# LB_BIT_i16_PULSE-v02_rev1.net
KiCad netlist of a schematic drawn in EAGLE
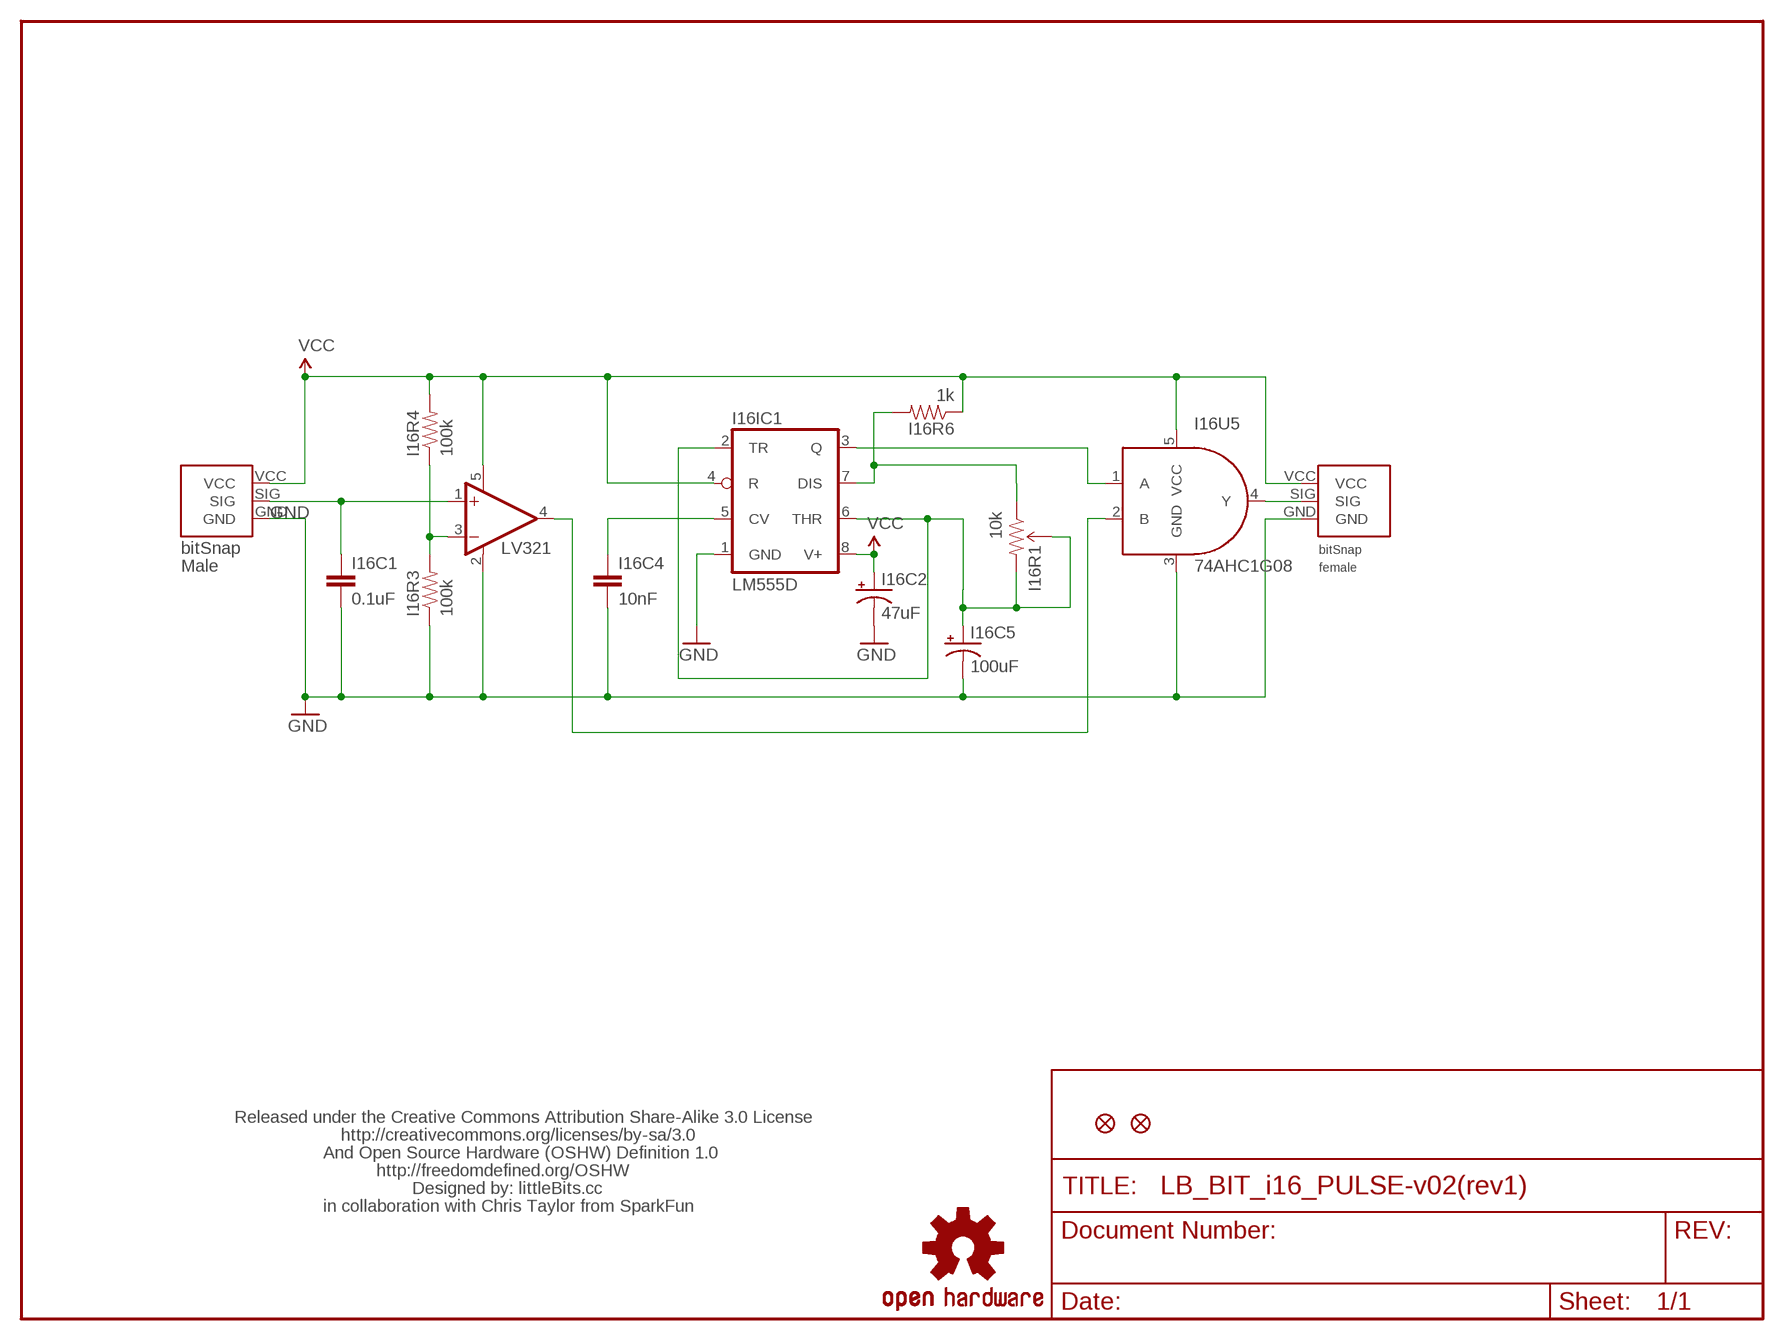
[diagram p0: schematic, sheet 1]

(export (version "E")
  (design (tool "Eeschema 10.0.6"))
  (components
    (comp (ref "I16BSF")
      (value "BITSNAP_FEMALE")
      (footprint "eagle-import:BITSNAP_FEMALE")
      (libsource (lib "eagle-import") (part "BITSNAP_FEMALE"))
    )
    (comp (ref "I16BSM")
      (value "BITSNAP_MALE")
      (footprint "eagle-import:BITSNAP_MALE")
      (libsource (lib "eagle-import") (part "BITSNAP_MALE"))
    )
    (comp (ref "I16C1")
      (value "0.1uF")
      (footprint "eagle-import:0603-CAP")
      (libsource (lib "eagle-import") (part "CAP0603-CAP"))
    )
    (comp (ref "I16C2")
      (value "47uF")
      (footprint "eagle-import:EIA3528")
      (libsource (lib "eagle-import") (part "CAP_POL3528"))
    )
    (comp (ref "I16C4")
      (value "10nF")
      (footprint "eagle-import:0603-CAP")
      (libsource (lib "eagle-import") (part "CAP0603-CAP"))
    )
    (comp (ref "I16C5")
      (value "100uF")
      (footprint "eagle-import:PANASONIC_C")
      (libsource (lib "eagle-import") (part "CAP_POLC"))
    )
    (comp (ref "I16IC1")
      (value "LM555D")
      (footprint "eagle-import:SO08")
      (libsource (lib "eagle-import") (part "555DLM"))
    )
    (comp (ref "I16R1")
      (value "10k")
      (footprint "eagle-import:TRIMPOT-3MM")
      (libsource (lib "eagle-import") (part "TRIMPOTSMD"))
    )
    (comp (ref "I16R3")
      (value "100k")
      (footprint "eagle-import:0603-RES")
      (libsource (lib "eagle-import") (part "RESISTOR0603-RES"))
    )
    (comp (ref "I16R4")
      (value "100k")
      (footprint "eagle-import:0603-RES")
      (libsource (lib "eagle-import") (part "RESISTOR0603-RES"))
    )
    (comp (ref "I16R6")
      (value "1k")
      (footprint "eagle-import:0603-RES")
      (libsource (lib "eagle-import") (part "RESISTOR0603-RES"))
    )
    (comp (ref "I16U1")
      (value "LV321")
      (footprint "eagle-import:SC70")
      (libsource (lib "eagle-import") (part "LV321"))
    )
    (comp (ref "I16U5")
      (value "74AHC1G08")
      (footprint "eagle-import:SOT23-5")
      (libsource (lib "eagle-import") (part "74AHC1G08"))
    )
    (comp (ref "JP1")
      (value "FIDUCIAL1X2.5")
      (footprint "eagle-import:FIDUCIAL-1X2.5")
      (libsource (lib "eagle-import") (part "FIDUCIAL1X2.5"))
    )
    (comp (ref "JP2")
      (value "FIDUCIAL1X2.5")
      (footprint "eagle-import:FIDUCIAL-1X2.5")
      (libsource (lib "eagle-import") (part "FIDUCIAL1X2.5"))
    )
    (comp (ref "U$1")
      (value "LB_CREDITS")
      (footprint "eagle-import:OSHWCREDIT")
      (libsource (lib "eagle-import") (part "LB_CREDITS"))
    )
    (comp (ref "U$5")
      (value "OSHW-LOGOL")
      (footprint "eagle-import:OSHW-LOGO-L")
      (libsource (lib "eagle-import") (part "OSHW-LOGOL"))
    )
  )
  (nets
    (net (code "1") (name "GND") (class "Default")
      (node (ref "I16BSF") (pin "GND") (pinfunction "GND_GND") (pintype "bidirectional"))
      (node (ref "I16BSM") (pin "GND") (pinfunction "GND_GND") (pintype "bidirectional"))
      (node (ref "I16C1") (pin "2") (pinfunction "2_2") (pintype "passive"))
      (node (ref "I16C2") (pin "C") (pinfunction "-_C") (pintype "passive"))
      (node (ref "I16C4") (pin "2") (pinfunction "2_2") (pintype "passive"))
      (node (ref "I16C5") (pin "-") (pinfunction "-_-") (pintype "passive"))
      (node (ref "I16IC1") (pin "1") (pinfunction "GND_1") (pintype "power_in"))
      (node (ref "I16R3") (pin "1") (pinfunction "1_1") (pintype "passive"))
      (node (ref "I16U1") (pin "2") (pinfunction "V-_2") (pintype "power_in"))
      (node (ref "I16U5") (pin "3") (pinfunction "GND_3") (pintype "bidirectional"))
    )
    (net (code "2") (name "Net-(I16IC1-CV)") (class "Default")
      (node (ref "I16C4") (pin "1") (pinfunction "1_1") (pintype "passive"))
      (node (ref "I16IC1") (pin "5") (pinfunction "CV_5") (pintype "input"))
    )
    (net (code "3") (name "Net-(I16IC1-DIS)") (class "Default")
      (node (ref "I16IC1") (pin "7") (pinfunction "DIS_7") (pintype "input"))
      (node (ref "I16R1") (pin "1") (pinfunction "CCW_1") (pintype "passive"))
      (node (ref "I16R6") (pin "2") (pinfunction "2_2") (pintype "passive"))
    )
    (net (code "4") (name "Net-(I16IC1-Q)") (class "Default")
      (node (ref "I16IC1") (pin "3") (pinfunction "Q_3") (pintype "output"))
      (node (ref "I16U5") (pin "1") (pinfunction "A_1") (pintype "bidirectional"))
    )
    (net (code "5") (name "Net-(I16IC1-THR)") (class "Default")
      (node (ref "I16C5") (pin "+") (pinfunction "+_+") (pintype "passive"))
      (node (ref "I16IC1") (pin "2") (pinfunction "TR_2") (pintype "input"))
      (node (ref "I16IC1") (pin "6") (pinfunction "THR_6") (pintype "input"))
      (node (ref "I16R1") (pin "2") (pinfunction "WIPER_2") (pintype "passive"))
      (node (ref "I16R1") (pin "3") (pinfunction "CW_3") (pintype "passive"))
    )
    (net (code "6") (name "Net-(I16U1-+IN)") (class "Default")
      (node (ref "I16BSM") (pin "SIG") (pinfunction "SIG_SIG") (pintype "bidirectional"))
      (node (ref "I16C1") (pin "1") (pinfunction "1_1") (pintype "passive"))
      (node (ref "I16U1") (pin "1") (pinfunction "+IN_1") (pintype "input"))
    )
    (net (code "7") (name "Net-(I16U1--IN)") (class "Default")
      (node (ref "I16R3") (pin "2") (pinfunction "2_2") (pintype "passive"))
      (node (ref "I16R4") (pin "1") (pinfunction "1_1") (pintype "passive"))
      (node (ref "I16U1") (pin "3") (pinfunction "-IN_3") (pintype "input"))
    )
    (net (code "8") (name "Net-(I16U1-OUT)") (class "Default")
      (node (ref "I16U1") (pin "4") (pinfunction "OUT_4") (pintype "output"))
      (node (ref "I16U5") (pin "2") (pinfunction "B_2") (pintype "bidirectional"))
    )
    (net (code "9") (name "Net-(I16U5-Y)") (class "Default")
      (node (ref "I16BSF") (pin "SIG") (pinfunction "SIG_SIG") (pintype "bidirectional"))
      (node (ref "I16U5") (pin "4") (pinfunction "Y_4") (pintype "bidirectional"))
    )
    (net (code "10") (name "VCC") (class "Default")
      (node (ref "I16BSF") (pin "VCC") (pinfunction "VCC_VCC") (pintype "bidirectional"))
      (node (ref "I16BSM") (pin "VCC") (pinfunction "VCC_VCC") (pintype "bidirectional"))
      (node (ref "I16C2") (pin "A") (pinfunction "+_A") (pintype "passive"))
      (node (ref "I16IC1") (pin "4") (pinfunction "R_4") (pintype "input"))
      (node (ref "I16IC1") (pin "8") (pinfunction "V+_8") (pintype "power_in"))
      (node (ref "I16R4") (pin "2") (pinfunction "2_2") (pintype "passive"))
      (node (ref "I16R6") (pin "1") (pinfunction "1_1") (pintype "passive"))
      (node (ref "I16U1") (pin "5") (pinfunction "V+_5") (pintype "power_in"))
      (node (ref "I16U5") (pin "5") (pinfunction "VCC_5") (pintype "bidirectional"))
    )
  )
)
